# MumSchema.net
KiCad netlist of a schematic drawn in EAGLE
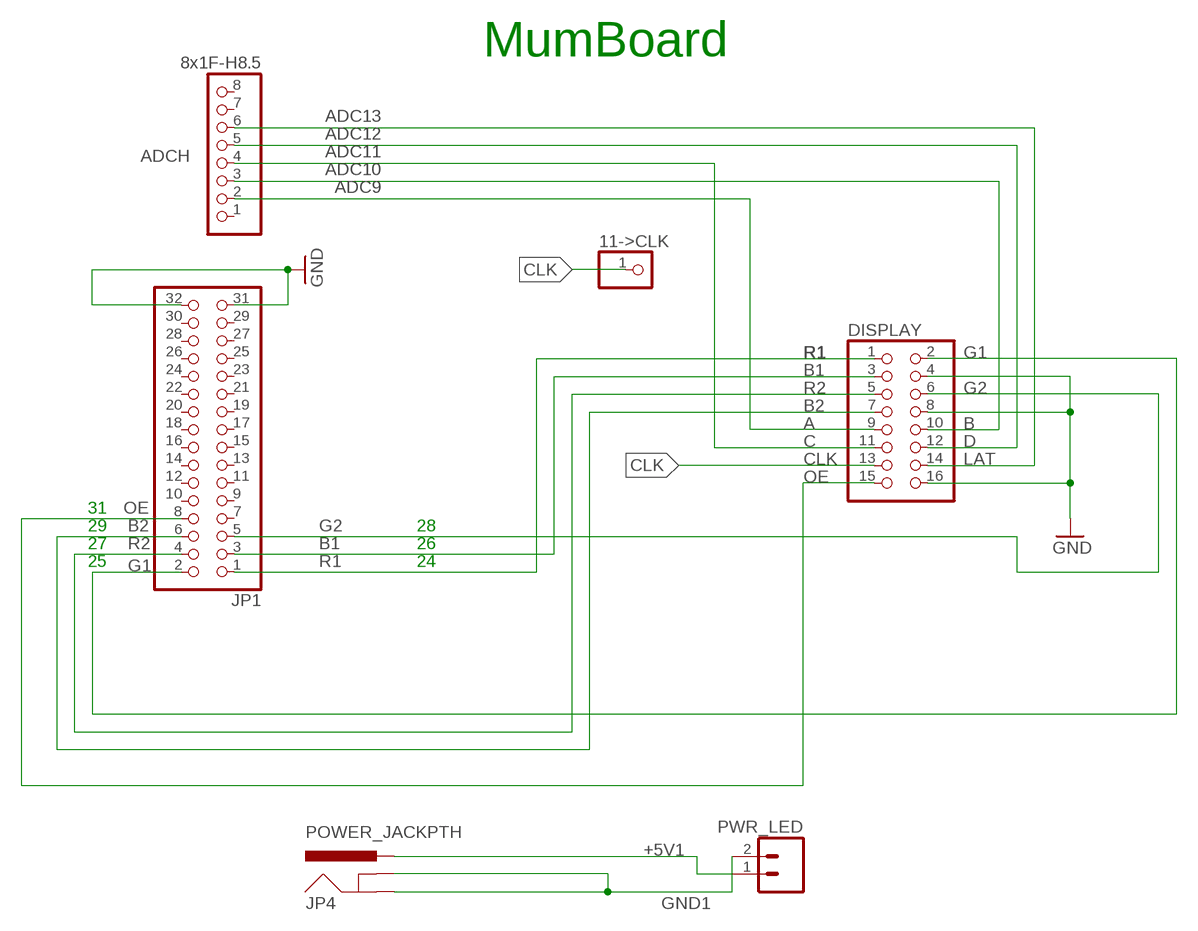
[diagram p0: schematic, sheet 1]

(export (version "E")
  (design (tool "Eeschema 10.0.6"))
  (components
    (comp (ref "11->CLK")
      (value "PINHD-1X1")
      (footprint "eagle-import:1X01")
      (libsource (lib "eagle-import") (part "PINHD-1X1"))
    )
    (comp (ref "ADCH")
      (value "8x1F-H8.5")
      (footprint "eagle-import:1X08")
      (fields (field (name "SPICEPREFIX") "A"))
      (libsource (lib "eagle-import") (part "PINHD-1X8"))
    )
    (comp (ref "DISPLAY")
      (value "PINHD-2X8")
      (footprint "eagle-import:2X08")
      (libsource (lib "eagle-import") (part "PINHD-2X8"))
    )
    (comp (ref "JP1")
      (value "PINHD-2X16")
      (footprint "eagle-import:2X16")
      (libsource (lib "eagle-import") (part "PINHD-2X16"))
    )
    (comp (ref "JP4")
      (value "POWER_JACKPTH")
      (footprint "eagle-import:POWER_JACK_PTH")
      (libsource (lib "eagle-import") (part "POWER_JACKPTH"))
    )
    (comp (ref "PWR_LED")
      (value "M023.5MM")
      (footprint "eagle-import:SCREWTERMINAL-3.5MM-2")
      (libsource (lib "eagle-import") (part "M023.5MM"))
    )
  )
  (nets
    (net (code "1") (name "/+5V1") (class "Default")
      (node (ref "JP4") (pin "PWR") (pinfunction "PWR_PWR") (pintype "bidirectional"))
      (node (ref "PWR_LED") (pin "1") (pinfunction "1_1") (pintype "passive"))
    )
    (net (code "2") (name "/A") (class "Default")
      (node (ref "ADCH") (pin "2") (pinfunction "2_2") (pintype "passive"))
      (node (ref "DISPLAY") (pin "9") (pinfunction "9_9") (pintype "passive"))
    )
    (net (code "3") (name "/ADC9") (class "Default")
      (node (ref "ADCH") (pin "3") (pinfunction "3_3") (pintype "passive"))
      (node (ref "DISPLAY") (pin "10") (pinfunction "10_10") (pintype "passive"))
    )
    (net (code "4") (name "/ADC10") (class "Default")
      (node (ref "ADCH") (pin "4") (pinfunction "4_4") (pintype "passive"))
      (node (ref "DISPLAY") (pin "11") (pinfunction "11_11") (pintype "passive"))
    )
    (net (code "5") (name "/ADC11") (class "Default")
      (node (ref "ADCH") (pin "5") (pinfunction "5_5") (pintype "passive"))
      (node (ref "DISPLAY") (pin "12") (pinfunction "12_12") (pintype "passive"))
    )
    (net (code "6") (name "/ADC12") (class "Default")
      (node (ref "ADCH") (pin "6") (pinfunction "6_6") (pintype "passive"))
      (node (ref "DISPLAY") (pin "14") (pinfunction "14_14") (pintype "passive"))
    )
    (net (code "8") (name "/B1") (class "Default")
      (node (ref "DISPLAY") (pin "3") (pinfunction "3_3") (pintype "passive"))
      (node (ref "JP1") (pin "3") (pinfunction "3_3") (pintype "passive"))
    )
    (net (code "9") (name "/B2") (class "Default")
      (node (ref "DISPLAY") (pin "7") (pinfunction "7_7") (pintype "passive"))
      (node (ref "JP1") (pin "6") (pinfunction "6_6") (pintype "passive"))
    )
    (net (code "10") (name "/G1") (class "Default")
      (node (ref "DISPLAY") (pin "2") (pinfunction "2_2") (pintype "passive"))
      (node (ref "JP1") (pin "2") (pinfunction "2_2") (pintype "passive"))
    )
    (net (code "11") (name "/G2") (class "Default")
      (node (ref "DISPLAY") (pin "6") (pinfunction "6_6") (pintype "passive"))
      (node (ref "JP1") (pin "5") (pinfunction "5_5") (pintype "passive"))
    )
    (net (code "12") (name "/GND1") (class "Default")
      (node (ref "JP4") (pin "GND") (pinfunction "GND_GND") (pintype "bidirectional"))
      (node (ref "JP4") (pin "GNDBREAK") (pinfunction "GNDBREAK_GNDBREAK") (pintype "bidirectional"))
      (node (ref "PWR_LED") (pin "2") (pinfunction "2_2") (pintype "passive"))
    )
    (net (code "13") (name "/OE") (class "Default")
      (node (ref "DISPLAY") (pin "15") (pinfunction "15_15") (pintype "passive"))
      (node (ref "JP1") (pin "8") (pinfunction "8_8") (pintype "passive"))
    )
    (net (code "14") (name "/R1") (class "Default")
      (node (ref "DISPLAY") (pin "1") (pinfunction "1_1") (pintype "passive"))
      (node (ref "JP1") (pin "1") (pinfunction "1_1") (pintype "passive"))
    )
    (net (code "15") (name "/R2") (class "Default")
      (node (ref "DISPLAY") (pin "5") (pinfunction "5_5") (pintype "passive"))
      (node (ref "JP1") (pin "4") (pinfunction "4_4") (pintype "passive"))
    )
    (net (code "16") (name "CLK") (class "Default")
      (node (ref "11->CLK") (pin "1") (pinfunction "1_1") (pintype "passive"))
      (node (ref "DISPLAY") (pin "13") (pinfunction "13_13") (pintype "passive"))
    )
    (net (code "17") (name "GND") (class "Default")
      (node (ref "DISPLAY") (pin "16") (pinfunction "16_16") (pintype "passive"))
      (node (ref "DISPLAY") (pin "4") (pinfunction "4_4") (pintype "passive"))
      (node (ref "DISPLAY") (pin "8") (pinfunction "8_8") (pintype "passive"))
      (node (ref "JP1") (pin "31") (pinfunction "31_31") (pintype "passive"))
      (node (ref "JP1") (pin "32") (pinfunction "32_32") (pintype "passive"))
    )
    (net (code "18") (name "unconnected-(ADCH-Pad1)") (class "Default")
      (node (ref "ADCH") (pin "1") (pinfunction "1_1") (pintype "passive"))
    )
    (net (code "19") (name "unconnected-(ADCH-Pad7)") (class "Default")
      (node (ref "ADCH") (pin "7") (pinfunction "7_7") (pintype "passive"))
    )
    (net (code "20") (name "unconnected-(ADCH-Pad8)") (class "Default")
      (node (ref "ADCH") (pin "8") (pinfunction "8_8") (pintype "passive"))
    )
    (net (code "21") (name "unconnected-(JP1-Pad7)") (class "Default")
      (node (ref "JP1") (pin "7") (pinfunction "7_7") (pintype "passive"))
    )
    (net (code "22") (name "unconnected-(JP1-Pad9)") (class "Default")
      (node (ref "JP1") (pin "9") (pinfunction "9_9") (pintype "passive"))
    )
    (net (code "23") (name "unconnected-(JP1-Pad10)") (class "Default")
      (node (ref "JP1") (pin "10") (pinfunction "10_10") (pintype "passive"))
    )
    (net (code "24") (name "unconnected-(JP1-Pad11)") (class "Default")
      (node (ref "JP1") (pin "11") (pinfunction "11_11") (pintype "passive"))
    )
    (net (code "25") (name "unconnected-(JP1-Pad12)") (class "Default")
      (node (ref "JP1") (pin "12") (pinfunction "12_12") (pintype "passive"))
    )
    (net (code "26") (name "unconnected-(JP1-Pad13)") (class "Default")
      (node (ref "JP1") (pin "13") (pinfunction "13_13") (pintype "passive"))
    )
    (net (code "27") (name "unconnected-(JP1-Pad14)") (class "Default")
      (node (ref "JP1") (pin "14") (pinfunction "14_14") (pintype "passive"))
    )
    (net (code "28") (name "unconnected-(JP1-Pad15)") (class "Default")
      (node (ref "JP1") (pin "15") (pinfunction "15_15") (pintype "passive"))
    )
    (net (code "29") (name "unconnected-(JP1-Pad16)") (class "Default")
      (node (ref "JP1") (pin "16") (pinfunction "16_16") (pintype "passive"))
    )
    (net (code "30") (name "unconnected-(JP1-Pad17)") (class "Default")
      (node (ref "JP1") (pin "17") (pinfunction "17_17") (pintype "passive"))
    )
    (net (code "31") (name "unconnected-(JP1-Pad18)") (class "Default")
      (node (ref "JP1") (pin "18") (pinfunction "18_18") (pintype "passive"))
    )
    (net (code "32") (name "unconnected-(JP1-Pad19)") (class "Default")
      (node (ref "JP1") (pin "19") (pinfunction "19_19") (pintype "passive"))
    )
    (net (code "33") (name "unconnected-(JP1-Pad20)") (class "Default")
      (node (ref "JP1") (pin "20") (pinfunction "20_20") (pintype "passive"))
    )
    (net (code "34") (name "unconnected-(JP1-Pad21)") (class "Default")
      (node (ref "JP1") (pin "21") (pinfunction "21_21") (pintype "passive"))
    )
    (net (code "35") (name "unconnected-(JP1-Pad22)") (class "Default")
      (node (ref "JP1") (pin "22") (pinfunction "22_22") (pintype "passive"))
    )
    (net (code "36") (name "unconnected-(JP1-Pad23)") (class "Default")
      (node (ref "JP1") (pin "23") (pinfunction "23_23") (pintype "passive"))
    )
    (net (code "37") (name "unconnected-(JP1-Pad24)") (class "Default")
      (node (ref "JP1") (pin "24") (pinfunction "24_24") (pintype "passive"))
    )
    (net (code "38") (name "unconnected-(JP1-Pad25)") (class "Default")
      (node (ref "JP1") (pin "25") (pinfunction "25_25") (pintype "passive"))
    )
    (net (code "39") (name "unconnected-(JP1-Pad26)") (class "Default")
      (node (ref "JP1") (pin "26") (pinfunction "26_26") (pintype "passive"))
    )
    (net (code "40") (name "unconnected-(JP1-Pad27)") (class "Default")
      (node (ref "JP1") (pin "27") (pinfunction "27_27") (pintype "passive"))
    )
    (net (code "41") (name "unconnected-(JP1-Pad28)") (class "Default")
      (node (ref "JP1") (pin "28") (pinfunction "28_28") (pintype "passive"))
    )
    (net (code "42") (name "unconnected-(JP1-Pad29)") (class "Default")
      (node (ref "JP1") (pin "29") (pinfunction "29_29") (pintype "passive"))
    )
    (net (code "43") (name "unconnected-(JP1-Pad30)") (class "Default")
      (node (ref "JP1") (pin "30") (pinfunction "30_30") (pintype "passive"))
    )
  )
)
